# ISPnubMod.net
KiCad netlist of a schematic drawn in EAGLE
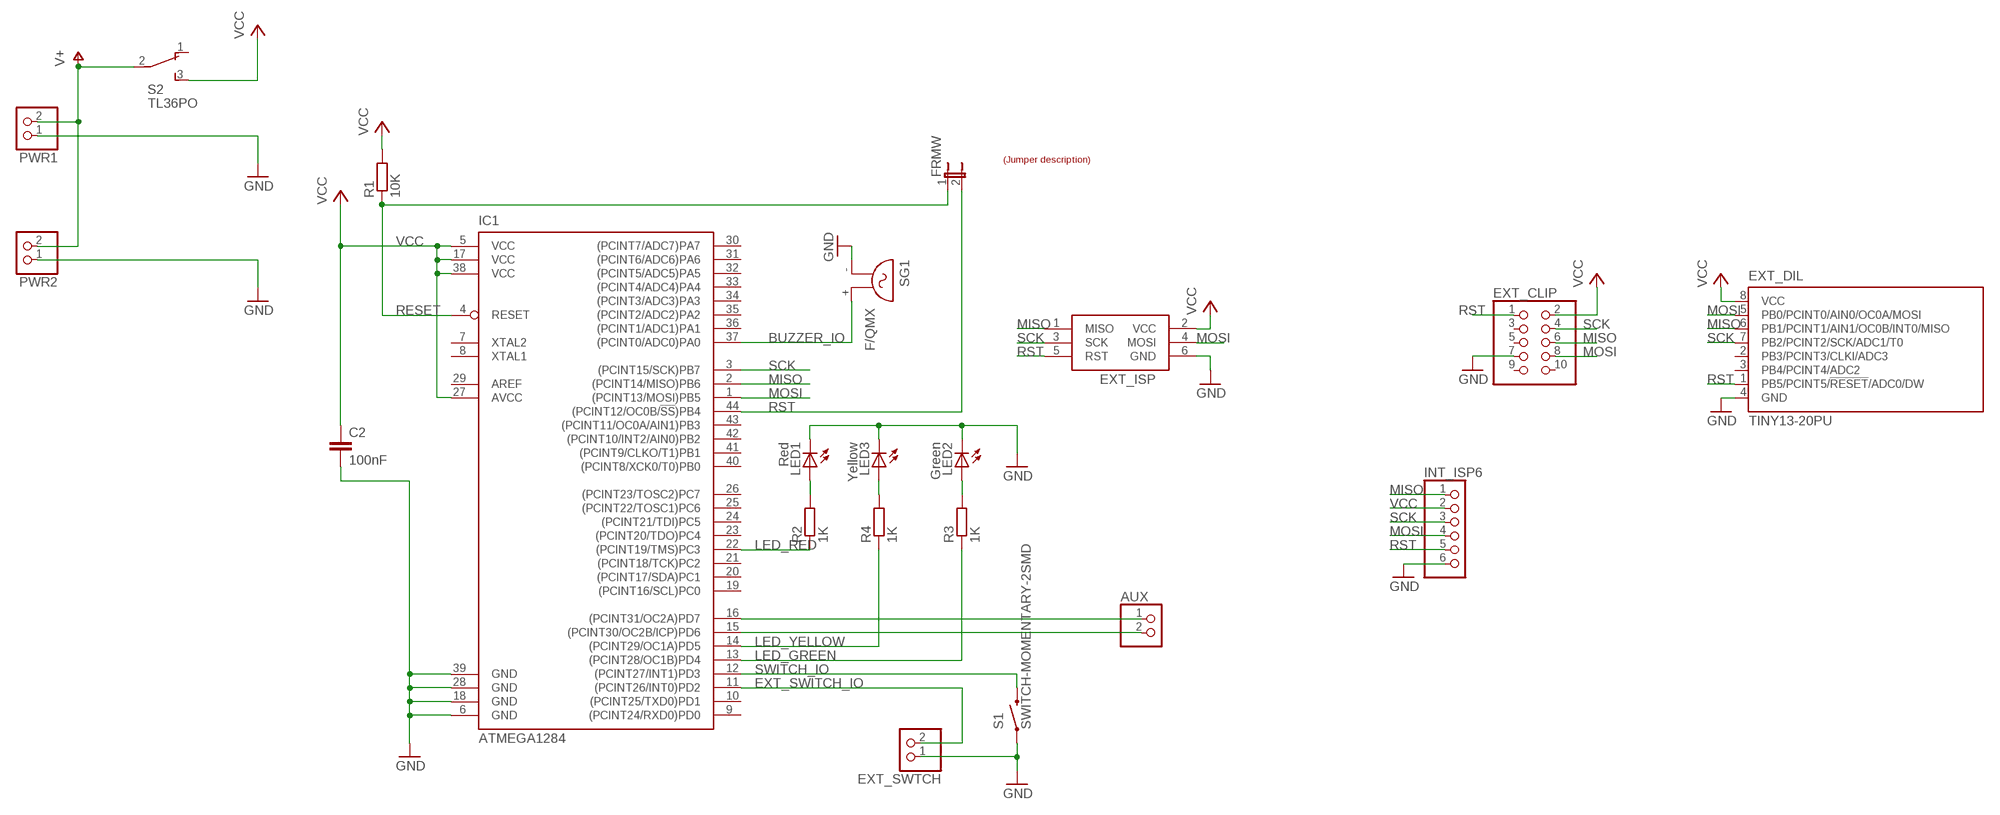
[diagram p0: schematic, sheet 1]

(export (version "E")
  (design (tool "Eeschema 10.0.6"))
  (components
    (comp (ref "AUX")
      (value "PINHD-1X2")
      (footprint "eagle-import:1X02")
      (libsource (lib "eagle-import") (part "PINHD-1X2"))
    )
    (comp (ref "C2")
      (value "100nF")
      (footprint "eagle-import:C0805")
      (libsource (lib "eagle-import") (part "C-EUC0805"))
    )
    (comp (ref "EXT_CLIP")
      (value "PINHD-2X5")
      (footprint "eagle-import:2X05")
      (libsource (lib "eagle-import") (part "PINHD-2X5"))
    )
    (comp (ref "EXT_DIL")
      (value "TINY13-20PU")
      (footprint "eagle-import:DIL08")
      (fields (field (name "MPN") "ATTINY13-20PU"))
      (libsource (lib "eagle-import") (part "TINY13PU-20"))
    )
    (comp (ref "EXT_ISP")
      (value "AVRISP-6")
      (footprint "eagle-import:AVRISP")
      (libsource (lib "eagle-import") (part "AVRISP-6"))
    )
    (comp (ref "EXT_SWTCH")
      (value "PINHD-1X2")
      (footprint "eagle-import:1X02")
      (libsource (lib "eagle-import") (part "PINHD-1X2"))
    )
    (comp (ref "FRMW")
      (value "JP1E")
      (footprint "eagle-import:JP1")
      (libsource (lib "eagle-import") (part "JP1E"))
    )
    (comp (ref "IC1")
      (value "ATMEGA1284")
      (footprint "eagle-import:TQFP44")
      (fields (field (name "MPN") "ATMEGA644PV-10AU") (field (name "MPN_1") "ATMEGA1284PV-10AU"))
      (libsource (lib "eagle-import") (part "ATMEGA644A"))
    )
    (comp (ref "INT_ISP6")
      (value "PINHD-1X6")
      (footprint "eagle-import:1X06")
      (libsource (lib "eagle-import") (part "PINHD-1X6"))
    )
    (comp (ref "LED1")
      (value "Red")
      (footprint "eagle-import:CHIP-LED0805")
      (libsource (lib "eagle-import") (part "LEDCHIP-LED0805"))
    )
    (comp (ref "LED2")
      (value "Green")
      (footprint "eagle-import:CHIP-LED0805")
      (libsource (lib "eagle-import") (part "LEDCHIP-LED0805"))
    )
    (comp (ref "LED3")
      (value "Yellow")
      (footprint "eagle-import:CHIP-LED0805")
      (libsource (lib "eagle-import") (part "LEDCHIP-LED0805"))
    )
    (comp (ref "PWR1")
      (value "PINHD-1X2")
      (footprint "eagle-import:1X02")
      (libsource (lib "eagle-import") (part "PINHD-1X2"))
    )
    (comp (ref "PWR2")
      (value "PINHD-1X2")
      (footprint "eagle-import:1X02")
      (libsource (lib "eagle-import") (part "PINHD-1X2"))
    )
    (comp (ref "R1")
      (value "10K")
      (footprint "eagle-import:R0805")
      (libsource (lib "eagle-import") (part "R-EU_R0805"))
    )
    (comp (ref "R2")
      (value "1K")
      (footprint "eagle-import:R0805")
      (libsource (lib "eagle-import") (part "R-EU_R0805"))
    )
    (comp (ref "R3")
      (value "1K")
      (footprint "eagle-import:R0805")
      (libsource (lib "eagle-import") (part "R-EU_R0805"))
    )
    (comp (ref "R4")
      (value "1K")
      (footprint "eagle-import:R0805")
      (libsource (lib "eagle-import") (part "R-EU_R0805"))
    )
    (comp (ref "S1")
      (value "SWITCH-MOMENTARY-2SMD")
      (footprint "eagle-import:TACTILE_SWITCH_SMD")
      (libsource (lib "eagle-import") (part "SWITCH-MOMENTARY-2SMD"))
    )
    (comp (ref "S2")
      (value "TL36PO")
      (footprint "eagle-import:TL3XPO")
      (libsource (lib "eagle-import") (part "TL36PO"))
    )
    (comp (ref "SG1")
      (value "F/QMX")
      (footprint "eagle-import:F_QMX")
      (libsource (lib "eagle-import") (part "F/QMX"))
    )
    (comp (ref "U$1")
      (value "LABEL_JUMPER_1X2")
      (footprint "eagle-import:JUMP2_DESC")
      (fields (field (name "OFF") "Normal") (field (name "ON") "Update Firmware"))
      (libsource (lib "eagle-import") (part "LABEL_JUMPER_1X2"))
    )
  )
  (nets
    (net (code "1") (name "/BUZZER_IO") (class "Default")
      (node (ref "IC1") (pin "37") (pinfunction "(PCINT0/ADC0)PA0_37") (pintype "bidirectional"))
      (node (ref "SG1") (pin "+") (pinfunction "2_+") (pintype "passive"))
    )
    (net (code "2") (name "/EXT_SWITCH_IO") (class "Default")
      (node (ref "EXT_SWTCH") (pin "2") (pinfunction "2_2") (pintype "passive"))
      (node (ref "IC1") (pin "11") (pinfunction "(PCINT26/INT0)PD2_11") (pintype "bidirectional"))
    )
    (net (code "3") (name "/LED_GREEN") (class "Default")
      (node (ref "IC1") (pin "13") (pinfunction "(PCINT28/OC1B)PD4_13") (pintype "bidirectional"))
      (node (ref "R3") (pin "1") (pinfunction "1_1") (pintype "passive"))
    )
    (net (code "4") (name "/LED_RED") (class "Default")
      (node (ref "IC1") (pin "22") (pinfunction "(PCINT19/TMS)PC3_22") (pintype "output"))
      (node (ref "R2") (pin "1") (pinfunction "1_1") (pintype "passive"))
    )
    (net (code "5") (name "/LED_YELLOW") (class "Default")
      (node (ref "IC1") (pin "14") (pinfunction "(PCINT29/OC1A)PD5_14") (pintype "bidirectional"))
      (node (ref "R4") (pin "1") (pinfunction "1_1") (pintype "passive"))
    )
    (net (code "6") (name "/MISO") (class "Default")
      (node (ref "EXT_CLIP") (pin "6") (pinfunction "6_6") (pintype "passive"))
      (node (ref "EXT_DIL") (pin "6") (pinfunction "PB1/PCINT1/AIN1/OC0B/INT0/MISO_6") (pintype "bidirectional"))
      (node (ref "EXT_ISP") (pin "1") (pinfunction "MISO_1") (pintype "input"))
      (node (ref "IC1") (pin "2") (pinfunction "(PCINT14/MISO)PB6_2") (pintype "bidirectional"))
      (node (ref "INT_ISP6") (pin "1") (pinfunction "1_1") (pintype "passive"))
    )
    (net (code "7") (name "/MOSI") (class "Default")
      (node (ref "EXT_CLIP") (pin "8") (pinfunction "8_8") (pintype "passive"))
      (node (ref "EXT_DIL") (pin "5") (pinfunction "PB0/PCINT0/AIN0/OC0A/MOSI_5") (pintype "bidirectional"))
      (node (ref "EXT_ISP") (pin "4") (pinfunction "MOSI_4") (pintype "output"))
      (node (ref "IC1") (pin "1") (pinfunction "(PCINT13/MOSI)PB5_1") (pintype "bidirectional"))
      (node (ref "INT_ISP6") (pin "4") (pinfunction "4_4") (pintype "passive"))
    )
    (net (code "8") (name "/RESET") (class "Default")
      (node (ref "FRMW") (pin "1") (pinfunction "1_1") (pintype "passive"))
      (node (ref "IC1") (pin "4") (pinfunction "RESET_4") (pintype "input"))
      (node (ref "R1") (pin "1") (pinfunction "1_1") (pintype "passive"))
    )
    (net (code "9") (name "/RST") (class "Default")
      (node (ref "EXT_CLIP") (pin "1") (pinfunction "1_1") (pintype "passive"))
      (node (ref "EXT_DIL") (pin "1") (pinfunction "PB5/PCINT5/~{RESET}/ADC0/DW_1") (pintype "bidirectional"))
      (node (ref "EXT_ISP") (pin "5") (pinfunction "RST_5") (pintype "output"))
      (node (ref "FRMW") (pin "2") (pinfunction "2_2") (pintype "passive"))
      (node (ref "IC1") (pin "44") (pinfunction "(PCINT12/OC0B/~{SS})PB4_44") (pintype "bidirectional"))
      (node (ref "INT_ISP6") (pin "5") (pinfunction "5_5") (pintype "passive"))
    )
    (net (code "10") (name "/SCK") (class "Default")
      (node (ref "EXT_CLIP") (pin "4") (pinfunction "4_4") (pintype "passive"))
      (node (ref "EXT_DIL") (pin "7") (pinfunction "PB2/PCINT2/SCK/ADC1/T0_7") (pintype "bidirectional"))
      (node (ref "EXT_ISP") (pin "3") (pinfunction "SCK_3") (pintype "output"))
      (node (ref "IC1") (pin "3") (pinfunction "(PCINT15/SCK)PB7_3") (pintype "bidirectional"))
      (node (ref "INT_ISP6") (pin "3") (pinfunction "3_3") (pintype "passive"))
    )
    (net (code "11") (name "/SWITCH_IO") (class "Default")
      (node (ref "IC1") (pin "12") (pinfunction "(PCINT27/INT1)PD3_12") (pintype "bidirectional"))
      (node (ref "S1") (pin "3") (pinfunction "2_3") (pintype "passive"))
    )
    (net (code "12") (name "GND") (class "Default")
      (node (ref "C2") (pin "2") (pinfunction "2_2") (pintype "passive"))
      (node (ref "EXT_CLIP") (pin "7") (pinfunction "7_7") (pintype "passive"))
      (node (ref "EXT_DIL") (pin "4") (pinfunction "GND_4") (pintype "power_in"))
      (node (ref "EXT_ISP") (pin "6") (pinfunction "GND_6") (pintype "power_in"))
      (node (ref "EXT_SWTCH") (pin "1") (pinfunction "1_1") (pintype "passive"))
      (node (ref "IC1") (pin "18") (pinfunction "GND_18") (pintype "power_in"))
      (node (ref "IC1") (pin "28") (pinfunction "GND_28") (pintype "power_in"))
      (node (ref "IC1") (pin "39") (pinfunction "GND_39") (pintype "power_in"))
      (node (ref "IC1") (pin "6") (pinfunction "GND_6") (pintype "power_in"))
      (node (ref "INT_ISP6") (pin "6") (pinfunction "6_6") (pintype "passive"))
      (node (ref "LED1") (pin "C") (pinfunction "C_C") (pintype "passive"))
      (node (ref "LED2") (pin "C") (pinfunction "C_C") (pintype "passive"))
      (node (ref "LED3") (pin "C") (pinfunction "C_C") (pintype "passive"))
      (node (ref "PWR1") (pin "1") (pinfunction "1_1") (pintype "passive"))
      (node (ref "PWR2") (pin "1") (pinfunction "1_1") (pintype "passive"))
      (node (ref "S1") (pin "1") (pinfunction "1_1") (pintype "passive"))
      (node (ref "SG1") (pin "-") (pinfunction "1_-") (pintype "passive"))
    )
    (net (code "13") (name "Net-(IC1-(PCINT30{slash}OC2B{slash}ICP)PD6)") (class "Default")
      (node (ref "AUX") (pin "2") (pinfunction "2_2") (pintype "passive"))
      (node (ref "IC1") (pin "15") (pinfunction "(PCINT30/OC2B/ICP)PD6_15") (pintype "bidirectional"))
    )
    (net (code "14") (name "Net-(IC1-(PCINT31{slash}OC2A)PD7)") (class "Default")
      (node (ref "AUX") (pin "1") (pinfunction "1_1") (pintype "passive"))
      (node (ref "IC1") (pin "16") (pinfunction "(PCINT31/OC2A)PD7_16") (pintype "bidirectional"))
    )
    (net (code "15") (name "Net-(LED1-PadA)") (class "Default")
      (node (ref "LED1") (pin "A") (pinfunction "A_A") (pintype "passive"))
      (node (ref "R2") (pin "2") (pinfunction "2_2") (pintype "passive"))
    )
    (net (code "16") (name "Net-(LED2-PadA)") (class "Default")
      (node (ref "LED2") (pin "A") (pinfunction "A_A") (pintype "passive"))
      (node (ref "R3") (pin "2") (pinfunction "2_2") (pintype "passive"))
    )
    (net (code "17") (name "Net-(LED3-PadA)") (class "Default")
      (node (ref "LED3") (pin "A") (pinfunction "A_A") (pintype "passive"))
      (node (ref "R4") (pin "2") (pinfunction "2_2") (pintype "passive"))
    )
    (net (code "18") (name "V+") (class "Default")
      (node (ref "PWR1") (pin "2") (pinfunction "2_2") (pintype "passive"))
      (node (ref "PWR2") (pin "2") (pinfunction "2_2") (pintype "passive"))
      (node (ref "S2") (pin "2") (pinfunction "P_2") (pintype "passive"))
    )
    (net (code "19") (name "VCC") (class "Default")
      (node (ref "C2") (pin "1") (pinfunction "1_1") (pintype "passive"))
      (node (ref "EXT_CLIP") (pin "2") (pinfunction "2_2") (pintype "passive"))
      (node (ref "EXT_DIL") (pin "8") (pinfunction "VCC_8") (pintype "power_in"))
      (node (ref "EXT_ISP") (pin "2") (pinfunction "VCC_2") (pintype "power_in"))
      (node (ref "IC1") (pin "17") (pinfunction "VCC_17") (pintype "power_in"))
      (node (ref "IC1") (pin "27") (pinfunction "AVCC_27") (pintype "power_in"))
      (node (ref "IC1") (pin "38") (pinfunction "VCC_38") (pintype "power_in"))
      (node (ref "IC1") (pin "5") (pinfunction "VCC_5") (pintype "power_in"))
      (node (ref "INT_ISP6") (pin "2") (pinfunction "2_2") (pintype "passive"))
      (node (ref "R1") (pin "2") (pinfunction "2_2") (pintype "passive"))
      (node (ref "S2") (pin "3") (pinfunction "S_3") (pintype "passive"))
    )
    (net (code "20") (name "unconnected-(EXT_CLIP-Pad3)") (class "Default")
      (node (ref "EXT_CLIP") (pin "3") (pinfunction "3_3") (pintype "passive"))
    )
    (net (code "21") (name "unconnected-(EXT_CLIP-Pad5)") (class "Default")
      (node (ref "EXT_CLIP") (pin "5") (pinfunction "5_5") (pintype "passive"))
    )
    (net (code "22") (name "unconnected-(EXT_CLIP-Pad9)") (class "Default")
      (node (ref "EXT_CLIP") (pin "9") (pinfunction "9_9") (pintype "passive"))
    )
    (net (code "23") (name "unconnected-(EXT_CLIP-Pad10)") (class "Default")
      (node (ref "EXT_CLIP") (pin "10") (pinfunction "10_10") (pintype "passive"))
    )
    (net (code "24") (name "unconnected-(EXT_DIL-PB3{slash}PCINT3{slash}CLKI{slash}ADC3-Pad2)") (class "Default")
      (node (ref "EXT_DIL") (pin "2") (pinfunction "PB3/PCINT3/CLKI/ADC3_2") (pintype "bidirectional"))
    )
    (net (code "25") (name "unconnected-(EXT_DIL-PB4{slash}PCINT4{slash}ADC2-Pad3)") (class "Default")
      (node (ref "EXT_DIL") (pin "3") (pinfunction "PB4/PCINT4/ADC2_3") (pintype "bidirectional"))
    )
    (net (code "26") (name "unconnected-(IC1-(PCINT1{slash}ADC1)PA1-Pad36)") (class "Default")
      (node (ref "IC1") (pin "36") (pinfunction "(PCINT1/ADC1)PA1_36") (pintype "bidirectional"))
    )
    (net (code "27") (name "unconnected-(IC1-(PCINT2{slash}ADC2)PA2-Pad35)") (class "Default")
      (node (ref "IC1") (pin "35") (pinfunction "(PCINT2/ADC2)PA2_35") (pintype "bidirectional"))
    )
    (net (code "28") (name "unconnected-(IC1-(PCINT3{slash}ADC3)PA3-Pad34)") (class "Default")
      (node (ref "IC1") (pin "34") (pinfunction "(PCINT3/ADC3)PA3_34") (pintype "bidirectional"))
    )
    (net (code "29") (name "unconnected-(IC1-(PCINT4{slash}ADC4)PA4-Pad33)") (class "Default")
      (node (ref "IC1") (pin "33") (pinfunction "(PCINT4/ADC4)PA4_33") (pintype "bidirectional"))
    )
    (net (code "30") (name "unconnected-(IC1-(PCINT5{slash}ADC5)PA5-Pad32)") (class "Default")
      (node (ref "IC1") (pin "32") (pinfunction "(PCINT5/ADC5)PA5_32") (pintype "bidirectional"))
    )
    (net (code "31") (name "unconnected-(IC1-(PCINT6{slash}ADC6)PA6-Pad31)") (class "Default")
      (node (ref "IC1") (pin "31") (pinfunction "(PCINT6/ADC6)PA6_31") (pintype "bidirectional"))
    )
    (net (code "32") (name "unconnected-(IC1-(PCINT7{slash}ADC7)PA7-Pad30)") (class "Default")
      (node (ref "IC1") (pin "30") (pinfunction "(PCINT7/ADC7)PA7_30") (pintype "bidirectional"))
    )
    (net (code "33") (name "unconnected-(IC1-(PCINT8{slash}XCK0{slash}T0)PB0-Pad40)") (class "Default")
      (node (ref "IC1") (pin "40") (pinfunction "(PCINT8/XCK0/T0)PB0_40") (pintype "bidirectional"))
    )
    (net (code "34") (name "unconnected-(IC1-(PCINT9{slash}CLKO{slash}T1)PB1-Pad41)") (class "Default")
      (node (ref "IC1") (pin "41") (pinfunction "(PCINT9/CLKO/T1)PB1_41") (pintype "bidirectional"))
    )
    (net (code "35") (name "unconnected-(IC1-(PCINT10{slash}INT2{slash}AIN0)PB2-Pad42)") (class "Default")
      (node (ref "IC1") (pin "42") (pinfunction "(PCINT10/INT2/AIN0)PB2_42") (pintype "bidirectional"))
    )
    (net (code "36") (name "unconnected-(IC1-(PCINT11{slash}OC0A{slash}AIN1)PB3-Pad43)") (class "Default")
      (node (ref "IC1") (pin "43") (pinfunction "(PCINT11/OC0A/AIN1)PB3_43") (pintype "bidirectional"))
    )
    (net (code "37") (name "unconnected-(IC1-(PCINT16{slash}SCL)PC0-Pad19)") (class "Default")
      (node (ref "IC1") (pin "19") (pinfunction "(PCINT16/SCL)PC0_19") (pintype "output"))
    )
    (net (code "38") (name "unconnected-(IC1-(PCINT17{slash}SDA)PC1-Pad20)") (class "Default")
      (node (ref "IC1") (pin "20") (pinfunction "(PCINT17/SDA)PC1_20") (pintype "output"))
    )
    (net (code "39") (name "unconnected-(IC1-(PCINT18{slash}TCK)PC2-Pad21)") (class "Default")
      (node (ref "IC1") (pin "21") (pinfunction "(PCINT18/TCK)PC2_21") (pintype "output"))
    )
    (net (code "40") (name "unconnected-(IC1-(PCINT20{slash}TDO)PC4-Pad23)") (class "Default")
      (node (ref "IC1") (pin "23") (pinfunction "(PCINT20/TDO)PC4_23") (pintype "output"))
    )
    (net (code "41") (name "unconnected-(IC1-(PCINT21{slash}TDI)PC5-Pad24)") (class "Default")
      (node (ref "IC1") (pin "24") (pinfunction "(PCINT21/TDI)PC5_24") (pintype "output"))
    )
    (net (code "42") (name "unconnected-(IC1-(PCINT22{slash}TOSC1)PC6-Pad25)") (class "Default")
      (node (ref "IC1") (pin "25") (pinfunction "(PCINT22/TOSC1)PC6_25") (pintype "output"))
    )
    (net (code "43") (name "unconnected-(IC1-(PCINT23{slash}TOSC2)PC7-Pad26)") (class "Default")
      (node (ref "IC1") (pin "26") (pinfunction "(PCINT23/TOSC2)PC7_26") (pintype "output"))
    )
    (net (code "44") (name "unconnected-(IC1-(PCINT24{slash}RXD0)PD0-Pad9)") (class "Default")
      (node (ref "IC1") (pin "9") (pinfunction "(PCINT24/RXD0)PD0_9") (pintype "bidirectional"))
    )
    (net (code "45") (name "unconnected-(IC1-(PCINT25{slash}TXD0)PD1-Pad10)") (class "Default")
      (node (ref "IC1") (pin "10") (pinfunction "(PCINT25/TXD0)PD1_10") (pintype "bidirectional"))
    )
    (net (code "46") (name "unconnected-(IC1-AREF-Pad29)") (class "Default")
      (node (ref "IC1") (pin "29") (pinfunction "AREF_29") (pintype "passive"))
    )
    (net (code "47") (name "unconnected-(IC1-XTAL1-Pad8)") (class "Default")
      (node (ref "IC1") (pin "8") (pinfunction "XTAL1_8") (pintype "bidirectional"))
    )
    (net (code "48") (name "unconnected-(IC1-XTAL2-Pad7)") (class "Default")
      (node (ref "IC1") (pin "7") (pinfunction "XTAL2_7") (pintype "bidirectional"))
    )
    (net (code "49") (name "unconnected-(S2-O-Pad1)") (class "Default")
      (node (ref "S2") (pin "1") (pinfunction "O_1") (pintype "passive"))
    )
  )
)
